# max1614_bo.net
KiCad netlist of a schematic drawn in EAGLE
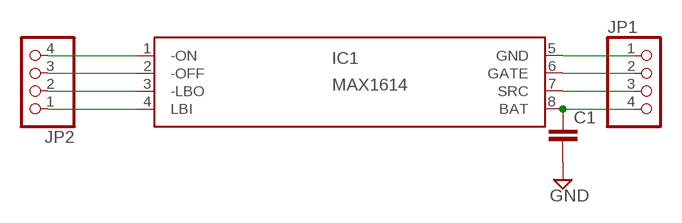
[diagram p0: schematic, sheet 1]

(export (version "E")
  (design (tool "Eeschema 10.0.6"))
  (components
    (comp (ref "C1")
      (value "C-EUC0805")
      (footprint "eagle-import:C0805")
      (libsource (lib "eagle-import") (part "C-EUC0805"))
    )
    (comp (ref "IC1")
      (value "MAX1614")
      (footprint "eagle-import:UMAX8")
      (libsource (lib "eagle-import") (part "MAX1614"))
    )
    (comp (ref "JP1")
      (value "PINHD-1X4")
      (footprint "eagle-import:1X04")
      (libsource (lib "eagle-import") (part "PINHD-1X4"))
    )
    (comp (ref "JP2")
      (value "PINHD-1X4")
      (footprint "eagle-import:1X04")
      (libsource (lib "eagle-import") (part "PINHD-1X4"))
    )
  )
  (nets
    (net (code "1") (name "GND") (class "Default")
      (node (ref "C1") (pin "2") (pinfunction "2_2") (pintype "passive"))
      (node (ref "IC1") (pin "5") (pinfunction "GND_5") (pintype "power_in"))
      (node (ref "JP1") (pin "1") (pinfunction "1_1") (pintype "passive"))
    )
    (net (code "2") (name "Net-(IC1--LBO)") (class "Default")
      (node (ref "IC1") (pin "3") (pinfunction "-LBO_3") (pintype "output"))
      (node (ref "JP2") (pin "2") (pinfunction "2_2") (pintype "passive"))
    )
    (net (code "3") (name "Net-(IC1--OFF)") (class "Default")
      (node (ref "IC1") (pin "2") (pinfunction "-OFF_2") (pintype "input"))
      (node (ref "JP2") (pin "3") (pinfunction "3_3") (pintype "passive"))
    )
    (net (code "4") (name "Net-(IC1--ON)") (class "Default")
      (node (ref "IC1") (pin "1") (pinfunction "-ON_1") (pintype "input"))
      (node (ref "JP2") (pin "4") (pinfunction "4_4") (pintype "passive"))
    )
    (net (code "5") (name "Net-(IC1-BAT)") (class "Default")
      (node (ref "C1") (pin "1") (pinfunction "1_1") (pintype "passive"))
      (node (ref "IC1") (pin "8") (pinfunction "BAT_8") (pintype "power_in"))
      (node (ref "JP1") (pin "4") (pinfunction "4_4") (pintype "passive"))
    )
    (net (code "6") (name "Net-(IC1-GATE)") (class "Default")
      (node (ref "IC1") (pin "6") (pinfunction "GATE_6") (pintype "output"))
      (node (ref "JP1") (pin "2") (pinfunction "2_2") (pintype "passive"))
    )
    (net (code "7") (name "Net-(IC1-LBI)") (class "Default")
      (node (ref "IC1") (pin "4") (pinfunction "LBI_4") (pintype "input"))
      (node (ref "JP2") (pin "1") (pinfunction "1_1") (pintype "passive"))
    )
    (net (code "8") (name "Net-(IC1-SRC)") (class "Default")
      (node (ref "IC1") (pin "7") (pinfunction "SRC_7") (pintype "input"))
      (node (ref "JP1") (pin "3") (pinfunction "3_3") (pintype "passive"))
    )
  )
)
